# Sheet1.net
KiCad netlist of a schematic drawn in Altium Designer
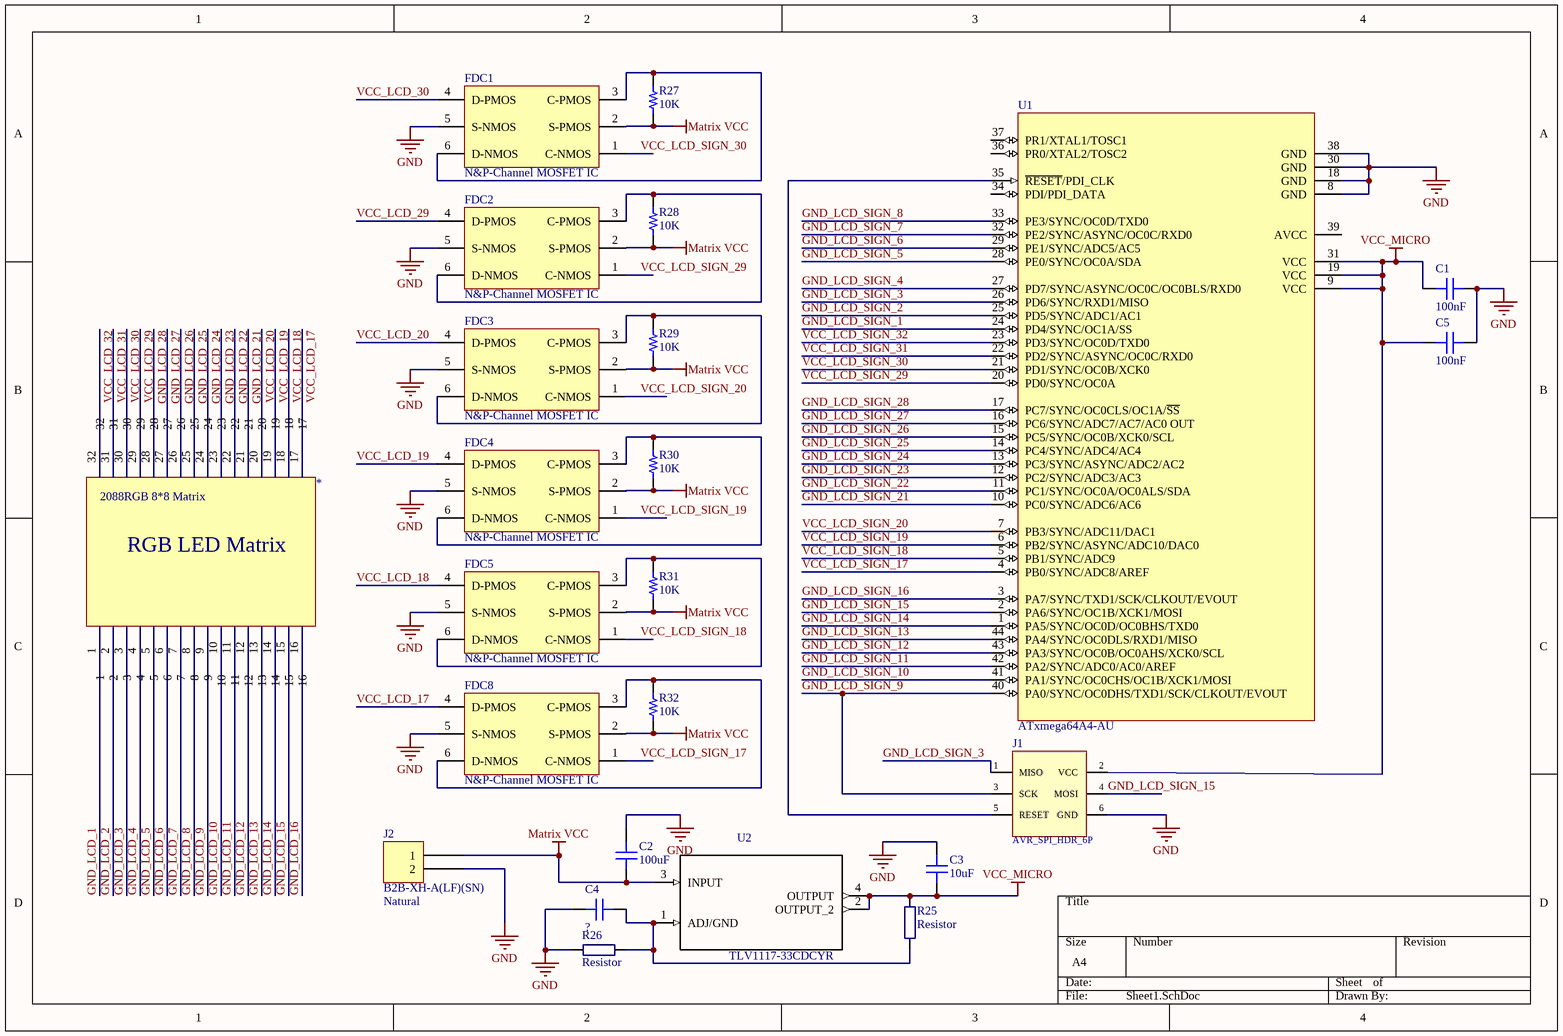
[diagram p0: Sheet1.SchDoc]

(export (version "E")
  (design (tool "Eeschema 10.0.6"))
  (components
    (comp (ref "*")
      (value "2088RGB 8*8 Matrix")
      (footprint "PCBComponent_1")
      (description "8*8 RGB Led Matrix")
      (libsource (lib "Schlib1") (part "2088RGB 8*8 Matrix"))
    )
    (comp (ref "C1")
      (value "100nF")
      (footprint "CAP 0603/1608")
      (description "CAP CER 82PF 50V C0G 0603")
      (fields (field (name "MANUFACTURER") "TDK Corporation") (field (name "TOLERANCE") "5%"))
      (libsource (lib "Celestial Library Database") (part "Capacitor"))
    )
    (comp (ref "C2")
      (value "100uF")
      (footprint "CAP 0603/1608")
      (description "CAP CER 82PF 50V C0G 0603")
      (fields (field (name "MANUFACTURER") "TDK Corporation") (field (name "TOLERANCE") "5%"))
      (libsource (lib "Celestial Library Database") (part "Capacitor"))
    )
    (comp (ref "C3")
      (value "10uF")
      (footprint "CAP 0603/1608")
      (description "CAP CER 82PF 50V C0G 0603")
      (fields (field (name "MANUFACTURER") "TDK Corporation") (field (name "TOLERANCE") "5%"))
      (libsource (lib "Celestial Library Database") (part "Capacitor"))
    )
    (comp (ref "C4")
      (value "?")
      (footprint "CAP 0603/1608")
      (description "CAP CER 82PF 50V C0G 0603")
      (fields (field (name "MANUFACTURER") "TDK Corporation") (field (name "TOLERANCE") "5%"))
      (libsource (lib "Celestial Library Database") (part "Capacitor"))
    )
    (comp (ref "C5")
      (value "100nF")
      (footprint "CAP 0603/1608")
      (description "CAP CER 82PF 50V C0G 0603")
      (fields (field (name "MANUFACTURER") "TDK Corporation") (field (name "TOLERANCE") "5%"))
      (libsource (lib "Celestial Library Database") (part "Capacitor"))
    )
    (comp (ref "FDC1")
      (value "N&P-Channel MOSFET IC")
      (footprint "SSOT-6")
      (libsource (lib "IC Chips") (part "FDC633C"))
    )
    (comp (ref "FDC2")
      (value "N&P-Channel MOSFET IC")
      (footprint "SSOT-6")
      (libsource (lib "IC Chips") (part "FDC633C"))
    )
    (comp (ref "FDC3")
      (value "N&P-Channel MOSFET IC")
      (footprint "SSOT-6")
      (libsource (lib "IC Chips") (part "FDC633C"))
    )
    (comp (ref "FDC4")
      (value "N&P-Channel MOSFET IC")
      (footprint "SSOT-6")
      (libsource (lib "IC Chips") (part "FDC633C"))
    )
    (comp (ref "FDC5")
      (value "N&P-Channel MOSFET IC")
      (footprint "SSOT-6")
      (libsource (lib "IC Chips") (part "FDC633C"))
    )
    (comp (ref "FDC8")
      (value "N&P-Channel MOSFET IC")
      (footprint "SSOT-6")
      (libsource (lib "IC Chips") (part "FDC633C"))
    )
    (comp (ref "J1")
      (value "AVR_SPI_HDR_6P")
      (footprint "HEADER_3x2")
      (libsource (lib "AVR_SPI_HDR_6P") (part "AVR_SPI_HDR_6P"))
    )
    (comp (ref "J2")
      (value "B2B-XH-A(LF)(SN)")
      (footprint "JST XH B2B-XH-A")
      (description "CONN HEADER XH TOP 2POS 2.5MM")
      (fields (field (name "COLOUR") "Natural") (field (name "MANUFACTURER") "JST Sales America Inc."))
      (libsource (lib "Celestial Library Database") (part "2 Pin"))
    )
    (comp (ref "R25")
      (value "Resistor")
      (footprint "RESC0603(1608)_N")
      (libsource (lib "Resistor") (part "Resistor"))
    )
    (comp (ref "R26")
      (value "Resistor")
      (footprint "RESC0603(1608)_N")
      (libsource (lib "Resistor") (part "Resistor"))
    )
    (comp (ref "R27")
      (value "10K")
      (footprint "RES 0603/1608")
      (description "RES SMD 232 OHM 1% 1/10W 0603")
      (fields (field (name "PART NUMBER") "ERJ-3EKF2320V"))
      (libsource (lib "Celestial Library Database") (part "Resistor"))
    )
    (comp (ref "R28")
      (value "10K")
      (footprint "RES 0603/1608")
      (description "RES SMD 232 OHM 1% 1/10W 0603")
      (fields (field (name "PART NUMBER") "ERJ-3EKF2320V"))
      (libsource (lib "Celestial Library Database") (part "Resistor"))
    )
    (comp (ref "R29")
      (value "10K")
      (footprint "RES 0603/1608")
      (description "RES SMD 232 OHM 1% 1/10W 0603")
      (fields (field (name "PART NUMBER") "ERJ-3EKF2320V"))
      (libsource (lib "Celestial Library Database") (part "Resistor"))
    )
    (comp (ref "R30")
      (value "10K")
      (footprint "RES 0603/1608")
      (description "RES SMD 232 OHM 1% 1/10W 0603")
      (fields (field (name "PART NUMBER") "ERJ-3EKF2320V"))
      (libsource (lib "Celestial Library Database") (part "Resistor"))
    )
    (comp (ref "R31")
      (value "10K")
      (footprint "RES 0603/1608")
      (description "RES SMD 232 OHM 1% 1/10W 0603")
      (fields (field (name "PART NUMBER") "ERJ-3EKF2320V"))
      (libsource (lib "Celestial Library Database") (part "Resistor"))
    )
    (comp (ref "R32")
      (value "10K")
      (footprint "RES 0603/1608")
      (description "RES SMD 232 OHM 1% 1/10W 0603")
      (fields (field (name "PART NUMBER") "ERJ-3EKF2320V"))
      (libsource (lib "Celestial Library Database") (part "Resistor"))
    )
    (comp (ref "U1")
      (value "ATxmega64A4-AU")
      (footprint "44A_N")
      (fields (field (name "PUBLISHER") "Altium Limited"))
      (libsource (lib "Atmel Microcontroller 8-16-Bit AVR XMEGA") (part "ATxmega64A4-AU"))
    )
    (comp (ref "U2")
      (value "TLV1117-33CDCYR")
      (footprint "SOT230P700X180-4N")
      (description "IC REG LIN 3.3V 800MA SOT223-4")
      (fields (field (name "MF") "Texas Instruments"))
      (libsource (lib "TLV1117-33CDCYR") (part "TLV1117-33CDCYR"))
    )
  )
  (nets
    (net (code "1") (name "/GND_LCD_1") (class "Default")
      (node (ref "*") (pin "1") (pinfunction "1_1") (pintype "passive"))
    )
    (net (code "2") (name "/GND_LCD_2") (class "Default")
      (node (ref "*") (pin "2") (pinfunction "2_2") (pintype "passive"))
    )
    (net (code "3") (name "/GND_LCD_3") (class "Default")
      (node (ref "*") (pin "3") (pinfunction "3_3") (pintype "passive"))
    )
    (net (code "4") (name "/GND_LCD_4") (class "Default")
      (node (ref "*") (pin "4") (pinfunction "4_4") (pintype "passive"))
    )
    (net (code "5") (name "/GND_LCD_5") (class "Default")
      (node (ref "*") (pin "5") (pinfunction "5_5") (pintype "passive"))
    )
    (net (code "6") (name "/GND_LCD_6") (class "Default")
      (node (ref "*") (pin "6") (pinfunction "6_6") (pintype "passive"))
    )
    (net (code "7") (name "/GND_LCD_7") (class "Default")
      (node (ref "*") (pin "7") (pinfunction "7_7") (pintype "passive"))
    )
    (net (code "8") (name "/GND_LCD_8") (class "Default")
      (node (ref "*") (pin "8") (pinfunction "8_8") (pintype "passive"))
    )
    (net (code "9") (name "/GND_LCD_9") (class "Default")
      (node (ref "*") (pin "9") (pinfunction "9_9") (pintype "passive"))
    )
    (net (code "10") (name "/GND_LCD_10") (class "Default")
      (node (ref "*") (pin "10") (pinfunction "10_10") (pintype "passive"))
    )
    (net (code "11") (name "/GND_LCD_11") (class "Default")
      (node (ref "*") (pin "11") (pinfunction "11_11") (pintype "passive"))
    )
    (net (code "12") (name "/GND_LCD_12") (class "Default")
      (node (ref "*") (pin "12") (pinfunction "12_12") (pintype "passive"))
    )
    (net (code "13") (name "/GND_LCD_13") (class "Default")
      (node (ref "*") (pin "13") (pinfunction "13_13") (pintype "passive"))
    )
    (net (code "14") (name "/GND_LCD_14") (class "Default")
      (node (ref "*") (pin "14") (pinfunction "14_14") (pintype "passive"))
    )
    (net (code "15") (name "/GND_LCD_15") (class "Default")
      (node (ref "*") (pin "15") (pinfunction "15_15") (pintype "passive"))
    )
    (net (code "16") (name "/GND_LCD_16") (class "Default")
      (node (ref "*") (pin "16") (pinfunction "16_16") (pintype "passive"))
    )
    (net (code "17") (name "/GND_LCD_21") (class "Default")
      (node (ref "*") (pin "21") (pinfunction "21_21") (pintype "passive"))
    )
    (net (code "18") (name "/GND_LCD_22") (class "Default")
      (node (ref "*") (pin "22") (pinfunction "22_22") (pintype "passive"))
    )
    (net (code "19") (name "/GND_LCD_23") (class "Default")
      (node (ref "*") (pin "23") (pinfunction "23_23") (pintype "passive"))
    )
    (net (code "20") (name "/GND_LCD_24") (class "Default")
      (node (ref "*") (pin "24") (pinfunction "24_24") (pintype "passive"))
    )
    (net (code "21") (name "/GND_LCD_25") (class "Default")
      (node (ref "*") (pin "25") (pinfunction "25_25") (pintype "passive"))
    )
    (net (code "22") (name "/GND_LCD_26") (class "Default")
      (node (ref "*") (pin "26") (pinfunction "26_26") (pintype "passive"))
    )
    (net (code "23") (name "/GND_LCD_27") (class "Default")
      (node (ref "*") (pin "27") (pinfunction "27_27") (pintype "passive"))
    )
    (net (code "24") (name "/GND_LCD_28") (class "Default")
      (node (ref "*") (pin "28") (pinfunction "28_28") (pintype "passive"))
    )
    (net (code "25") (name "/GND_LCD_SIGN_1") (class "Default")
      (node (ref "U1") (pin "24") (pinfunction "PD4/SYNC/OC1A/SS_24") (pintype "bidirectional"))
    )
    (net (code "26") (name "/GND_LCD_SIGN_2") (class "Default")
      (node (ref "U1") (pin "25") (pinfunction "PD5/SYNC/ADC1/AC1_25") (pintype "bidirectional"))
    )
    (net (code "27") (name "/GND_LCD_SIGN_3") (class "Default")
      (node (ref "J1") (pin "1") (pinfunction "MISO_1") (pintype "passive"))
      (node (ref "U1") (pin "26") (pinfunction "PD6/SYNC/RXD1/MISO_26") (pintype "bidirectional"))
    )
    (net (code "28") (name "/GND_LCD_SIGN_4") (class "Default")
      (node (ref "U1") (pin "27") (pinfunction "PD7/SYNC/ASYNC/OC0C/OC0BLS/RXD0_27") (pintype "bidirectional"))
    )
    (net (code "29") (name "/GND_LCD_SIGN_5") (class "Default")
      (node (ref "U1") (pin "28") (pinfunction "PE0/SYNC/OC0A/SDA_28") (pintype "bidirectional"))
    )
    (net (code "30") (name "/GND_LCD_SIGN_6") (class "Default")
      (node (ref "U1") (pin "29") (pinfunction "PE1/SYNC/ADC5/AC5_29") (pintype "bidirectional"))
    )
    (net (code "31") (name "/GND_LCD_SIGN_7") (class "Default")
      (node (ref "U1") (pin "32") (pinfunction "PE2/SYNC/ASYNC/OC0C/RXD0_32") (pintype "bidirectional"))
    )
    (net (code "32") (name "/GND_LCD_SIGN_8") (class "Default")
      (node (ref "U1") (pin "33") (pinfunction "PE3/SYNC/OC0D/TXD0_33") (pintype "bidirectional"))
    )
    (net (code "33") (name "/GND_LCD_SIGN_9") (class "Default")
      (node (ref "J1") (pin "3") (pinfunction "SCK_3") (pintype "passive"))
      (node (ref "U1") (pin "40") (pinfunction "PA0/SYNC/OC0DHS/TXD1/SCK/CLKOUT/EVOUT_40") (pintype "bidirectional"))
    )
    (net (code "34") (name "/GND_LCD_SIGN_10") (class "Default")
      (node (ref "U1") (pin "41") (pinfunction "PA1/SYNC/OC0CHS/OC1B/XCK1/MOSI_41") (pintype "bidirectional"))
    )
    (net (code "35") (name "/GND_LCD_SIGN_11") (class "Default")
      (node (ref "U1") (pin "42") (pinfunction "PA2/SYNC/ADC0/AC0/AREF_42") (pintype "bidirectional"))
    )
    (net (code "36") (name "/GND_LCD_SIGN_12") (class "Default")
      (node (ref "U1") (pin "43") (pinfunction "PA3/SYNC/OC0B/OC0AHS/XCK0/SCL_43") (pintype "bidirectional"))
    )
    (net (code "37") (name "/GND_LCD_SIGN_13") (class "Default")
      (node (ref "U1") (pin "44") (pinfunction "PA4/SYNC/OC0DLS/RXD1/MISO_44") (pintype "bidirectional"))
    )
    (net (code "38") (name "/GND_LCD_SIGN_14") (class "Default")
      (node (ref "U1") (pin "1") (pinfunction "PA5/SYNC/OC0D/OC0BHS/TXD0_1") (pintype "bidirectional"))
    )
    (net (code "39") (name "/GND_LCD_SIGN_15") (class "Default")
      (node (ref "J1") (pin "4") (pinfunction "MOSI_4") (pintype "passive"))
      (node (ref "U1") (pin "2") (pinfunction "PA6/SYNC/OC1B/XCK1/MOSI_2") (pintype "bidirectional"))
    )
    (net (code "40") (name "/GND_LCD_SIGN_16") (class "Default")
      (node (ref "U1") (pin "3") (pinfunction "PA7/SYNC/TXD1/SCK/CLKOUT/EVOUT_3") (pintype "bidirectional"))
    )
    (net (code "41") (name "/GND_LCD_SIGN_21") (class "Default")
      (node (ref "U1") (pin "10") (pinfunction "PC0/SYNC/ADC6/AC6_10") (pintype "bidirectional"))
    )
    (net (code "42") (name "/GND_LCD_SIGN_22") (class "Default")
      (node (ref "U1") (pin "11") (pinfunction "PC1/SYNC/OC0A/OC0ALS/SDA_11") (pintype "bidirectional"))
    )
    (net (code "43") (name "/GND_LCD_SIGN_23") (class "Default")
      (node (ref "U1") (pin "12") (pinfunction "PC2/SYNC/ADC3/AC3_12") (pintype "bidirectional"))
    )
    (net (code "44") (name "/GND_LCD_SIGN_24") (class "Default")
      (node (ref "U1") (pin "13") (pinfunction "PC3/SYNC/ASYNC/ADC2/AC2_13") (pintype "bidirectional"))
    )
    (net (code "45") (name "/GND_LCD_SIGN_25") (class "Default")
      (node (ref "U1") (pin "14") (pinfunction "PC4/SYNC/ADC4/AC4_14") (pintype "bidirectional"))
    )
    (net (code "46") (name "/GND_LCD_SIGN_26") (class "Default")
      (node (ref "U1") (pin "15") (pinfunction "PC5/SYNC/OC0B/XCK0/SCL_15") (pintype "bidirectional"))
    )
    (net (code "47") (name "/GND_LCD_SIGN_27") (class "Default")
      (node (ref "U1") (pin "16") (pinfunction "PC6/SYNC/ADC7/AC7/AC0_OUT_16") (pintype "bidirectional"))
    )
    (net (code "48") (name "/GND_LCD_SIGN_28") (class "Default")
      (node (ref "U1") (pin "17") (pinfunction "PC7/SYNC/OC0CLS/OC1A/~{SS}_17") (pintype "bidirectional"))
    )
    (net (code "49") (name "/VCC_LCD_17") (class "Default")
      (node (ref "*") (pin "17") (pinfunction "17_17") (pintype "passive"))
      (node (ref "FDC8") (pin "4") (pinfunction "D-PMOS_4") (pintype "passive"))
    )
    (net (code "50") (name "/VCC_LCD_18") (class "Default")
      (node (ref "*") (pin "18") (pinfunction "18_18") (pintype "passive"))
      (node (ref "FDC5") (pin "4") (pinfunction "D-PMOS_4") (pintype "passive"))
    )
    (net (code "51") (name "/VCC_LCD_19") (class "Default")
      (node (ref "*") (pin "19") (pinfunction "19_19") (pintype "passive"))
      (node (ref "FDC4") (pin "4") (pinfunction "D-PMOS_4") (pintype "passive"))
    )
    (net (code "52") (name "/VCC_LCD_20") (class "Default")
      (node (ref "*") (pin "20") (pinfunction "20_20") (pintype "passive"))
      (node (ref "FDC3") (pin "4") (pinfunction "D-PMOS_4") (pintype "passive"))
    )
    (net (code "53") (name "/VCC_LCD_29") (class "Default")
      (node (ref "*") (pin "29") (pinfunction "29_29") (pintype "passive"))
      (node (ref "FDC2") (pin "4") (pinfunction "D-PMOS_4") (pintype "passive"))
    )
    (net (code "54") (name "/VCC_LCD_30") (class "Default")
      (node (ref "*") (pin "30") (pinfunction "30_30") (pintype "passive"))
      (node (ref "FDC1") (pin "4") (pinfunction "D-PMOS_4") (pintype "passive"))
    )
    (net (code "55") (name "/VCC_LCD_31") (class "Default")
      (node (ref "*") (pin "31") (pinfunction "31_31") (pintype "passive"))
    )
    (net (code "56") (name "/VCC_LCD_32") (class "Default")
      (node (ref "*") (pin "32") (pinfunction "32_32") (pintype "passive"))
    )
    (net (code "57") (name "/VCC_LCD_SIGN_17") (class "Default")
      (node (ref "FDC8") (pin "1") (pinfunction "C-NMOS_1") (pintype "passive"))
      (node (ref "U1") (pin "4") (pinfunction "PB0/SYNC/ADC8/AREF_4") (pintype "bidirectional"))
    )
    (net (code "58") (name "/VCC_LCD_SIGN_18") (class "Default")
      (node (ref "FDC5") (pin "1") (pinfunction "C-NMOS_1") (pintype "passive"))
      (node (ref "U1") (pin "5") (pinfunction "PB1/SYNC/ADC9_5") (pintype "bidirectional"))
    )
    (net (code "59") (name "/VCC_LCD_SIGN_19") (class "Default")
      (node (ref "FDC4") (pin "1") (pinfunction "C-NMOS_1") (pintype "passive"))
      (node (ref "U1") (pin "6") (pinfunction "PB2/SYNC/ASYNC/ADC10/DAC0_6") (pintype "bidirectional"))
    )
    (net (code "60") (name "/VCC_LCD_SIGN_20") (class "Default")
      (node (ref "FDC3") (pin "1") (pinfunction "C-NMOS_1") (pintype "passive"))
      (node (ref "U1") (pin "7") (pinfunction "PB3/SYNC/ADC11/DAC1_7") (pintype "bidirectional"))
    )
    (net (code "61") (name "/VCC_LCD_SIGN_29") (class "Default")
      (node (ref "FDC2") (pin "1") (pinfunction "C-NMOS_1") (pintype "passive"))
      (node (ref "U1") (pin "20") (pinfunction "PD0/SYNC/OC0A_20") (pintype "bidirectional"))
    )
    (net (code "62") (name "/VCC_LCD_SIGN_30") (class "Default")
      (node (ref "FDC1") (pin "1") (pinfunction "C-NMOS_1") (pintype "passive"))
      (node (ref "U1") (pin "21") (pinfunction "PD1/SYNC/OC0B/XCK0_21") (pintype "bidirectional"))
    )
    (net (code "63") (name "/VCC_LCD_SIGN_31") (class "Default")
      (node (ref "U1") (pin "22") (pinfunction "PD2/SYNC/ASYNC/OC0C/RXD0_22") (pintype "bidirectional"))
    )
    (net (code "64") (name "/VCC_LCD_SIGN_32") (class "Default")
      (node (ref "U1") (pin "23") (pinfunction "PD3/SYNC/OC0D/TXD0_23") (pintype "bidirectional"))
    )
    (net (code "65") (name "GND") (class "Default")
      (node (ref "C1") (pin "2") (pinfunction "2_2") (pintype "passive"))
      (node (ref "C2") (pin "2") (pinfunction "2_2") (pintype "passive"))
      (node (ref "C3") (pin "2") (pinfunction "2_2") (pintype "passive"))
      (node (ref "C4") (pin "2") (pinfunction "2_2") (pintype "passive"))
      (node (ref "C5") (pin "2") (pinfunction "2_2") (pintype "passive"))
      (node (ref "FDC1") (pin "5") (pinfunction "S-NMOS_5") (pintype "passive"))
      (node (ref "FDC2") (pin "5") (pinfunction "S-NMOS_5") (pintype "passive"))
      (node (ref "FDC3") (pin "5") (pinfunction "S-NMOS_5") (pintype "passive"))
      (node (ref "FDC4") (pin "5") (pinfunction "S-NMOS_5") (pintype "passive"))
      (node (ref "FDC5") (pin "5") (pinfunction "S-NMOS_5") (pintype "passive"))
      (node (ref "FDC8") (pin "5") (pinfunction "S-NMOS_5") (pintype "passive"))
      (node (ref "J1") (pin "6") (pinfunction "GND_6") (pintype "passive"))
      (node (ref "J2") (pin "2") (pinfunction "2_2") (pintype "passive"))
      (node (ref "R26") (pin "1") (pinfunction "1_1") (pintype "passive"))
      (node (ref "U1") (pin "18") (pinfunction "GND_18") (pintype "power_in"))
      (node (ref "U1") (pin "30") (pinfunction "GND_30") (pintype "power_in"))
      (node (ref "U1") (pin "38") (pinfunction "GND_38") (pintype "power_in"))
      (node (ref "U1") (pin "8") (pinfunction "GND_8") (pintype "power_in"))
    )
    (net (code "66") (name "Matrix VCC") (class "Default")
      (node (ref "C2") (pin "1") (pinfunction "1_1") (pintype "passive"))
      (node (ref "FDC1") (pin "2") (pinfunction "S-PMOS_2") (pintype "passive"))
      (node (ref "FDC2") (pin "2") (pinfunction "S-PMOS_2") (pintype "passive"))
      (node (ref "FDC3") (pin "2") (pinfunction "S-PMOS_2") (pintype "passive"))
      (node (ref "FDC4") (pin "2") (pinfunction "S-PMOS_2") (pintype "passive"))
      (node (ref "FDC5") (pin "2") (pinfunction "S-PMOS_2") (pintype "passive"))
      (node (ref "FDC8") (pin "2") (pinfunction "S-PMOS_2") (pintype "passive"))
      (node (ref "J2") (pin "1") (pinfunction "1_1") (pintype "passive"))
      (node (ref "R27") (pin "1") (pinfunction "1_1") (pintype "passive"))
      (node (ref "R28") (pin "1") (pinfunction "1_1") (pintype "passive"))
      (node (ref "R29") (pin "1") (pinfunction "1_1") (pintype "passive"))
      (node (ref "R30") (pin "1") (pinfunction "1_1") (pintype "passive"))
      (node (ref "R31") (pin "1") (pinfunction "1_1") (pintype "passive"))
      (node (ref "R32") (pin "1") (pinfunction "1_1") (pintype "passive"))
      (node (ref "U2") (pin "3") (pinfunction "INPUT_3") (pintype "input"))
    )
    (net (code "67") (name "Net-(FDC1-C-PMOS)") (class "Default")
      (node (ref "FDC1") (pin "3") (pinfunction "C-PMOS_3") (pintype "passive"))
      (node (ref "FDC1") (pin "6") (pinfunction "D-NMOS_6") (pintype "passive"))
      (node (ref "R27") (pin "2") (pinfunction "2_2") (pintype "passive"))
    )
    (net (code "68") (name "Net-(FDC2-C-PMOS)") (class "Default")
      (node (ref "FDC2") (pin "3") (pinfunction "C-PMOS_3") (pintype "passive"))
      (node (ref "FDC2") (pin "6") (pinfunction "D-NMOS_6") (pintype "passive"))
      (node (ref "R28") (pin "2") (pinfunction "2_2") (pintype "passive"))
    )
    (net (code "69") (name "Net-(FDC3-C-PMOS)") (class "Default")
      (node (ref "FDC3") (pin "3") (pinfunction "C-PMOS_3") (pintype "passive"))
      (node (ref "FDC3") (pin "6") (pinfunction "D-NMOS_6") (pintype "passive"))
      (node (ref "R29") (pin "2") (pinfunction "2_2") (pintype "passive"))
    )
    (net (code "70") (name "Net-(FDC4-C-PMOS)") (class "Default")
      (node (ref "FDC4") (pin "3") (pinfunction "C-PMOS_3") (pintype "passive"))
      (node (ref "FDC4") (pin "6") (pinfunction "D-NMOS_6") (pintype "passive"))
      (node (ref "R30") (pin "2") (pinfunction "2_2") (pintype "passive"))
    )
    (net (code "71") (name "Net-(FDC5-C-PMOS)") (class "Default")
      (node (ref "FDC5") (pin "3") (pinfunction "C-PMOS_3") (pintype "passive"))
      (node (ref "FDC5") (pin "6") (pinfunction "D-NMOS_6") (pintype "passive"))
      (node (ref "R31") (pin "2") (pinfunction "2_2") (pintype "passive"))
    )
    (net (code "72") (name "Net-(FDC8-C-PMOS)") (class "Default")
      (node (ref "FDC8") (pin "3") (pinfunction "C-PMOS_3") (pintype "passive"))
      (node (ref "FDC8") (pin "6") (pinfunction "D-NMOS_6") (pintype "passive"))
      (node (ref "R32") (pin "2") (pinfunction "2_2") (pintype "passive"))
    )
    (net (code "73") (name "Net-(J1-RESET)") (class "Default")
      (node (ref "J1") (pin "5") (pinfunction "RESET_5") (pintype "passive"))
      (node (ref "U1") (pin "35") (pinfunction "~{RESET}/PDI_CLK_35") (pintype "input"))
    )
    (net (code "74") (name "Net-(U2-ADJ{slash}GND)") (class "Default")
      (node (ref "C4") (pin "1") (pinfunction "1_1") (pintype "passive"))
      (node (ref "R25") (pin "1") (pinfunction "1_1") (pintype "passive"))
      (node (ref "R26") (pin "2") (pinfunction "2_2") (pintype "passive"))
      (node (ref "U2") (pin "1") (pinfunction "ADJ/GND_1") (pintype "input"))
    )
    (net (code "75") (name "VCC_MICRO") (class "Default")
      (node (ref "C1") (pin "1") (pinfunction "1_1") (pintype "passive"))
      (node (ref "C3") (pin "1") (pinfunction "1_1") (pintype "passive"))
      (node (ref "C5") (pin "1") (pinfunction "1_1") (pintype "passive"))
      (node (ref "J1") (pin "2") (pinfunction "VCC_2") (pintype "passive"))
      (node (ref "R25") (pin "2") (pinfunction "2_2") (pintype "passive"))
      (node (ref "U1") (pin "19") (pinfunction "VCC_19") (pintype "power_in"))
      (node (ref "U1") (pin "31") (pinfunction "VCC_31") (pintype "power_in"))
      (node (ref "U1") (pin "9") (pinfunction "VCC_9") (pintype "power_in"))
      (node (ref "U2") (pin "2") (pinfunction "OUTPUT_2_2") (pintype "output"))
      (node (ref "U2") (pin "4") (pinfunction "OUTPUT_4") (pintype "output"))
    )
    (net (code "76") (name "unconnected-(U1-AVCC-Pad39)") (class "Default")
      (node (ref "U1") (pin "39") (pinfunction "AVCC_39") (pintype "power_in"))
    )
    (net (code "77") (name "unconnected-(U1-PDI{slash}PDI_DATA-Pad34)") (class "Default")
      (node (ref "U1") (pin "34") (pinfunction "PDI/PDI_DATA_34") (pintype "bidirectional"))
    )
    (net (code "78") (name "unconnected-(U1-PR0{slash}XTAL2{slash}TOSC2-Pad36)") (class "Default")
      (node (ref "U1") (pin "36") (pinfunction "PR0/XTAL2/TOSC2_36") (pintype "bidirectional"))
    )
    (net (code "79") (name "unconnected-(U1-PR1{slash}XTAL1{slash}TOSC1-Pad37)") (class "Default")
      (node (ref "U1") (pin "37") (pinfunction "PR1/XTAL1/TOSC1_37") (pintype "bidirectional"))
    )
  )
)
